# GPS.net
KiCad netlist of a schematic drawn in Altium Designer
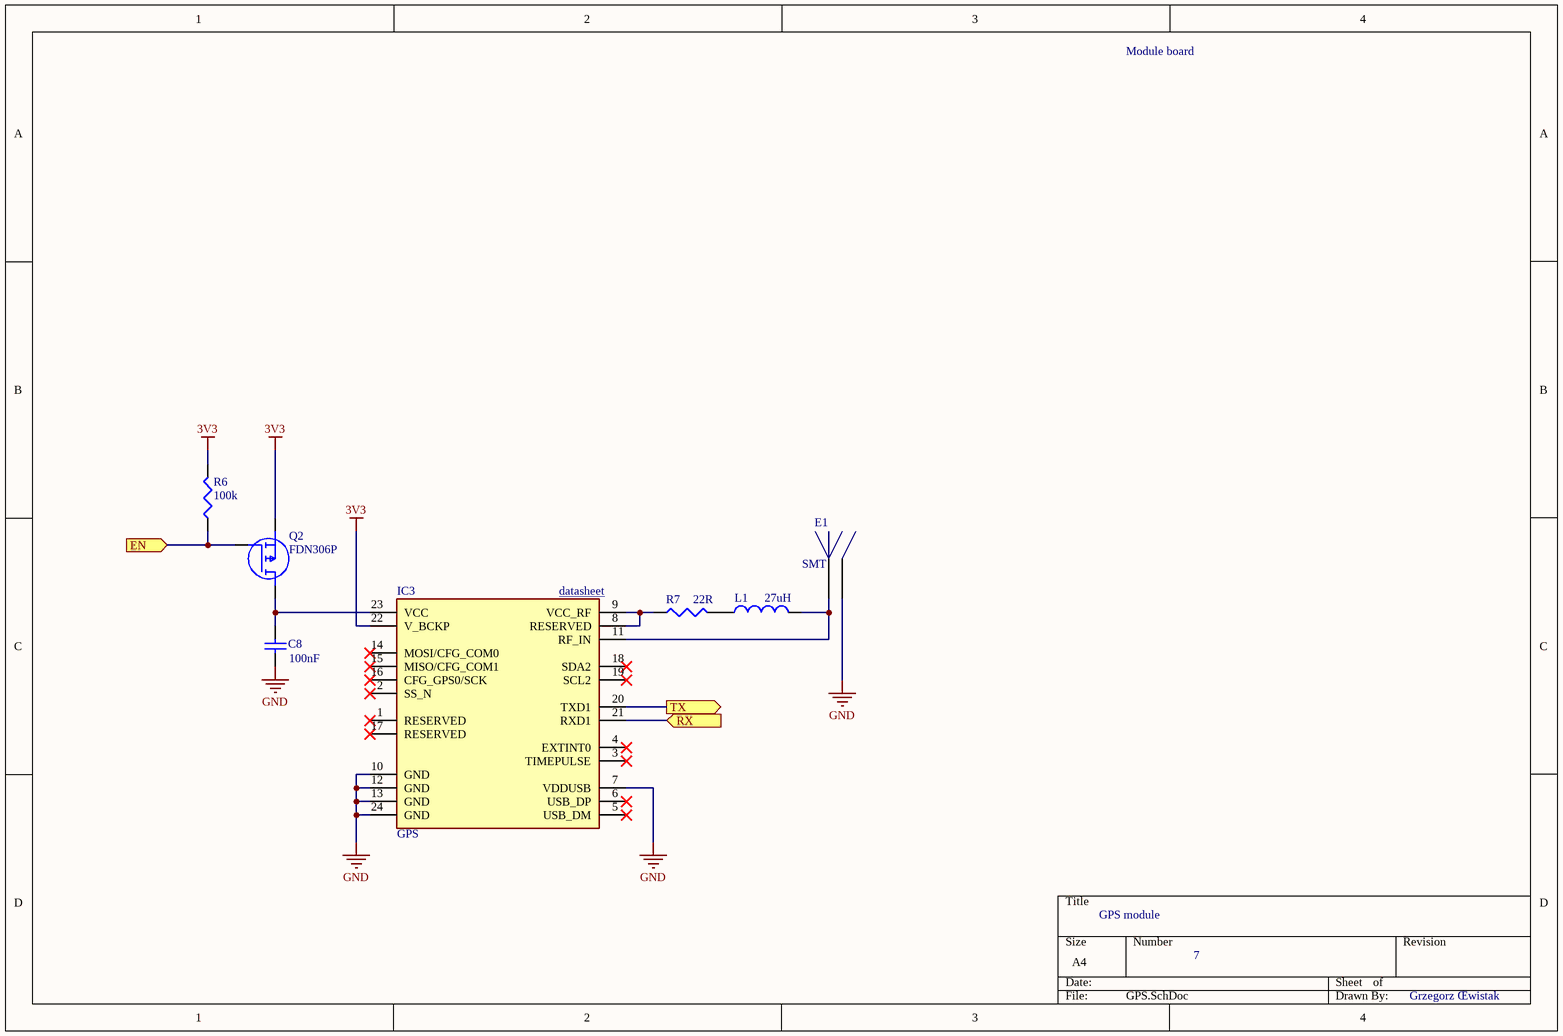
[diagram p0: GPS.SchDoc]

(export (version "E")
  (design (tool "Eeschema 10.0.6"))
  (components
    (comp (ref "C8")
      (value "100nF")
      (footprint "C0805")
      (description "Capacitor")
      (fields (field (name "Comment") "Cap") (field (name "PUBLISHER") "Altium Limited"))
      (libsource (lib "Miscellaneous Devices") (part "Cap"))
    )
    (comp (ref "E1") (value "SMT") (footprint "UFLRSMT160") (libsource (lib "lib") (part "SMT_antenne")))
    (comp (ref "IC3")
      (value "GPS")
      (footprint "NEO6M0001_only_used_pins")
      (description "GPS modle")
      (fields (field (name "MANUFACTURER_PART_NUMBER") "NEO-6M-0-001"))
      (libsource (lib "lib") (part "NEO-6M-0-001"))
    )
    (comp (ref "L1")
      (value "27uH")
      (footprint "L-0805")
      (description "Inductor")
      (fields (field (name "PUBLISHER") "Altium Limited"))
      (libsource (lib "Miscellaneous Devices") (part "Inductor"))
    )
    (comp (ref "Q2")
      (value "FDN306P")
      (footprint "SOT95P237X112-3N")
      (description "MOSFET (P-Channel)")
      (fields (field (name "MOUSER PART NUMBER") "512-FDN306P"))
      (libsource (lib "lib") (part "FDN306P"))
    )
    (comp (ref "R6")
      (value "100k")
      (footprint "R0603")
      (description "Resistor")
      (fields (field (name "Comment") "Res3") (field (name "PUBLISHER") "Altium Limited"))
      (libsource (lib "Miscellaneous Devices") (part "Res3"))
    )
    (comp (ref "R7")
      (value "22R")
      (footprint "R0603")
      (description "Resistor")
      (fields (field (name "PUBLISHER") "Altium Limited"))
      (libsource (lib "Miscellaneous Devices") (part "Res3"))
    )
  )
  (nets
    (net (code "1") (name "/EN") (class "Default")
      (node (ref "Q2") (pin "1") (pinfunction "G_1") (pintype "passive"))
      (node (ref "R6") (pin "1") (pinfunction "1_1") (pintype "passive"))
    )
    (net (code "2") (name "/RX") (class "Default")
      (node (ref "IC3") (pin "21") (pinfunction "RXD1_21") (pintype "passive"))
    )
    (net (code "3") (name "/TX") (class "Default")
      (node (ref "IC3") (pin "20") (pinfunction "TXD1_20") (pintype "passive"))
    )
    (net (code "4") (name "3V3") (class "Default")
      (node (ref "IC3") (pin "22") (pinfunction "V_BCKP_22") (pintype "passive"))
      (node (ref "Q2") (pin "2") (pinfunction "S_2") (pintype "passive"))
      (node (ref "R6") (pin "2") (pinfunction "2_2") (pintype "passive"))
    )
    (net (code "5") (name "GND") (class "Default")
      (node (ref "C8") (pin "1") (pinfunction "1_1") (pintype "passive"))
      (node (ref "E1") (pin "2") (pinfunction "GND_2") (pintype "passive"))
      (node (ref "IC3") (pin "10") (pinfunction "GND_10") (pintype "passive"))
      (node (ref "IC3") (pin "12") (pinfunction "GND_12") (pintype "passive"))
      (node (ref "IC3") (pin "13") (pinfunction "GND_13") (pintype "passive"))
      (node (ref "IC3") (pin "24") (pinfunction "GND_24") (pintype "passive"))
      (node (ref "IC3") (pin "7") (pinfunction "VDDUSB_7") (pintype "passive"))
    )
    (net (code "6") (name "Net-(E1-SIG)") (class "Default")
      (node (ref "E1") (pin "1") (pinfunction "SIG_1") (pintype "passive"))
      (node (ref "IC3") (pin "11") (pinfunction "RF_IN_11") (pintype "passive"))
      (node (ref "L1") (pin "2") (pinfunction "2_2") (pintype "passive"))
    )
    (net (code "7") (name "Net-(IC3-VCC)") (class "Default")
      (node (ref "C8") (pin "2") (pinfunction "2_2") (pintype "passive"))
      (node (ref "IC3") (pin "23") (pinfunction "VCC_23") (pintype "passive"))
      (node (ref "Q2") (pin "3") (pinfunction "D_3") (pintype "passive"))
    )
    (net (code "8") (name "Net-(IC3-VCC_RF)") (class "Default")
      (node (ref "IC3") (pin "8") (pinfunction "RESERVED_8") (pintype "passive"))
      (node (ref "IC3") (pin "9") (pinfunction "VCC_RF_9") (pintype "passive"))
      (node (ref "R7") (pin "1") (pinfunction "1_1") (pintype "passive"))
    )
    (net (code "9") (name "Net-(L1-Pad1)") (class "Default")
      (node (ref "L1") (pin "1") (pinfunction "1_1") (pintype "passive"))
      (node (ref "R7") (pin "2") (pinfunction "2_2") (pintype "passive"))
    )
    (net (code "10") (name "unconnected-(IC3-CFG_GPS0{slash}SCK-Pad16)") (class "Default")
      (node (ref "IC3") (pin "16") (pinfunction "CFG_GPS0/SCK_16") (pintype "passive+no_connect"))
    )
    (net (code "11") (name "unconnected-(IC3-EXTINT0-Pad4)") (class "Default")
      (node (ref "IC3") (pin "4") (pinfunction "EXTINT0_4") (pintype "passive+no_connect"))
    )
    (net (code "12") (name "unconnected-(IC3-MISO{slash}CFG_COM1-Pad15)") (class "Default")
      (node (ref "IC3") (pin "15") (pinfunction "MISO/CFG_COM1_15") (pintype "passive+no_connect"))
    )
    (net (code "13") (name "unconnected-(IC3-MOSI{slash}CFG_COM0-Pad14)") (class "Default")
      (node (ref "IC3") (pin "14") (pinfunction "MOSI/CFG_COM0_14") (pintype "passive+no_connect"))
    )
    (net (code "14") (name "unconnected-(IC3-RESERVED-Pad1)") (class "Default")
      (node (ref "IC3") (pin "1") (pinfunction "RESERVED_1") (pintype "passive+no_connect"))
    )
    (net (code "15") (name "unconnected-(IC3-RESERVED-Pad17)") (class "Default")
      (node (ref "IC3") (pin "17") (pinfunction "RESERVED_17") (pintype "passive+no_connect"))
    )
    (net (code "16") (name "unconnected-(IC3-SCL2-Pad19)") (class "Default")
      (node (ref "IC3") (pin "19") (pinfunction "SCL2_19") (pintype "passive+no_connect"))
    )
    (net (code "17") (name "unconnected-(IC3-SDA2-Pad18)") (class "Default")
      (node (ref "IC3") (pin "18") (pinfunction "SDA2_18") (pintype "passive+no_connect"))
    )
    (net (code "18") (name "unconnected-(IC3-SS_N-Pad2)") (class "Default")
      (node (ref "IC3") (pin "2") (pinfunction "SS_N_2") (pintype "passive+no_connect"))
    )
    (net (code "19") (name "unconnected-(IC3-TIMEPULSE-Pad3)") (class "Default")
      (node (ref "IC3") (pin "3") (pinfunction "TIMEPULSE_3") (pintype "passive+no_connect"))
    )
    (net (code "20") (name "unconnected-(IC3-USB_DM-Pad5)") (class "Default")
      (node (ref "IC3") (pin "5") (pinfunction "USB_DM_5") (pintype "passive+no_connect"))
    )
    (net (code "21") (name "unconnected-(IC3-USB_DP-Pad6)") (class "Default")
      (node (ref "IC3") (pin "6") (pinfunction "USB_DP_6") (pintype "passive+no_connect"))
    )
  )
)
